# POWER.net
KiCad netlist of a schematic drawn in Altium Designer
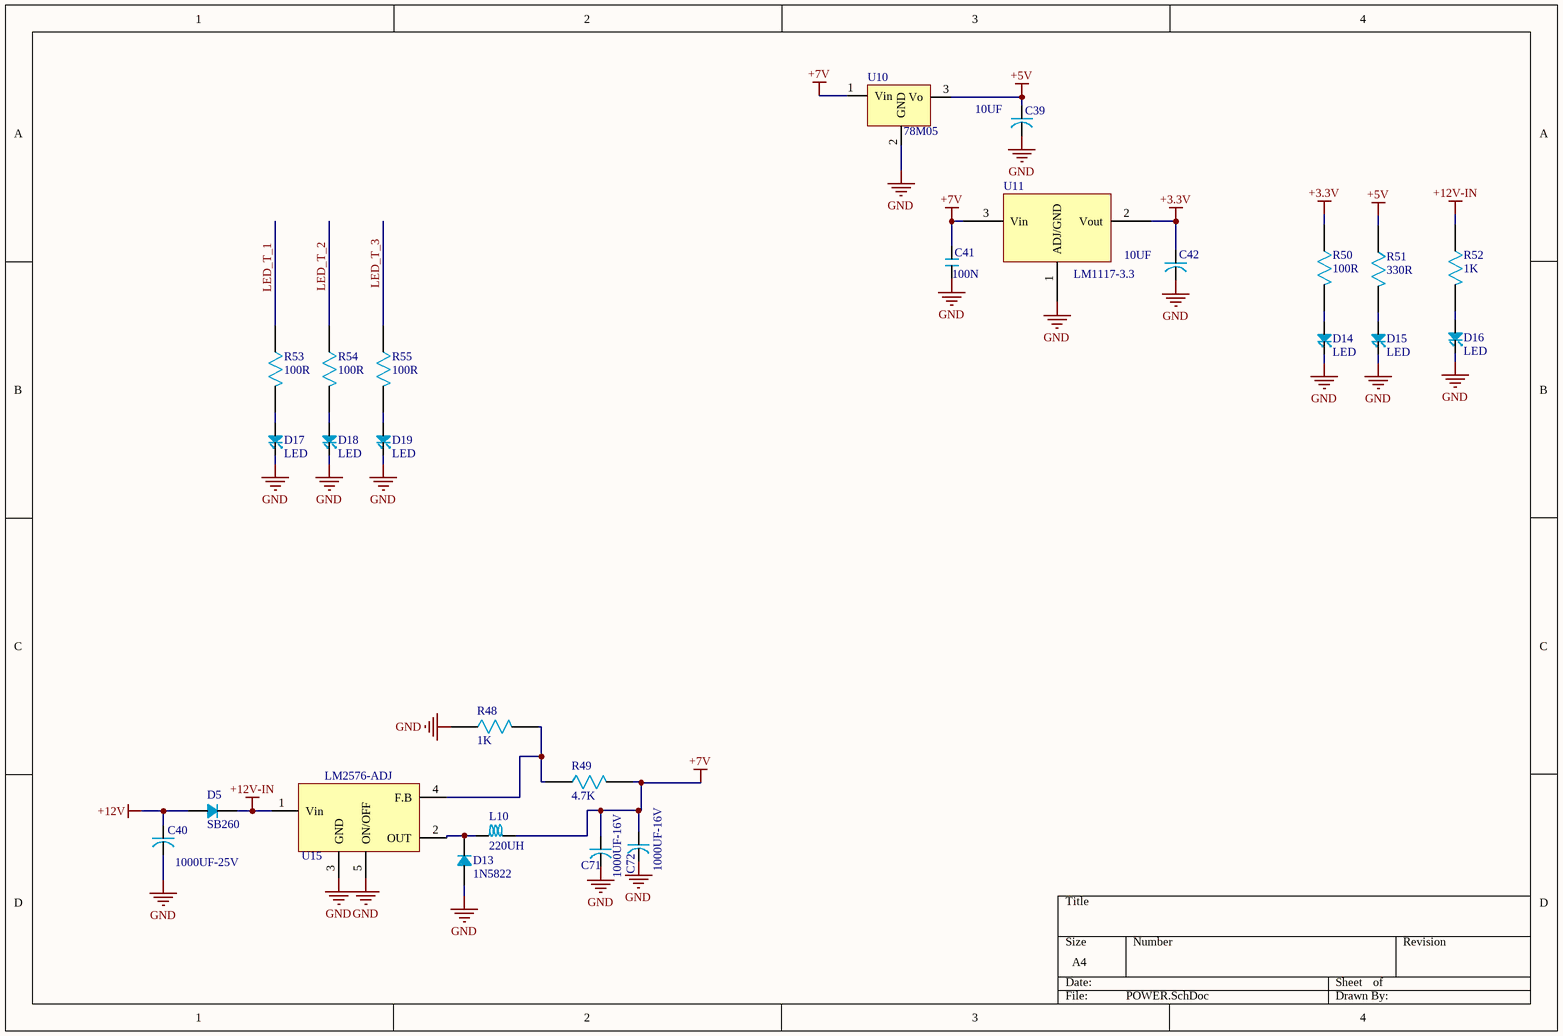
[diagram p0: POWER.SchDoc]

(export (version "E")
  (design (tool "Eeschema 10.0.6"))
  (components
    (comp (ref "C39") (value "10UF") (footprint "1206") (libsource (lib "") (part "CAP_POL_1")))
    (comp (ref "C40") (value "1000UF-25V") (footprint "RB.2/.4") (libsource (lib "") (part "CAP_POL_2")))
    (comp (ref "C41") (value "100N") (footprint "1206") (libsource (lib "R_L_C_V") (part "CAP")))
    (comp (ref "C42") (value "10UF") (footprint "1206") (libsource (lib "") (part "CAP_POL_1")))
    (comp (ref "C71") (value "1000UF-16V") (footprint "RB.2/.4") (libsource (lib "My_lib") (part "CAP_POL")))
    (comp (ref "C72") (value "1000UF-16V") (footprint "RB.2/.4") (libsource (lib "") (part "CAP_POL_1")))
    (comp (ref "D5") (value "SB260") (footprint "DIODE0.1") (libsource (lib "My_lib") (part "DIODE")))
    (comp (ref "D13") (value "1N5822") (footprint "SOD-123-B") (libsource (lib "R_L_C_V") (part "DIODE")))
    (comp (ref "D14") (value "LED") (footprint "0603") (libsource (lib "My_lib") (part "LED")))
    (comp (ref "D15") (value "LED") (footprint "0603") (libsource (lib "My_lib") (part "LED")))
    (comp (ref "D16") (value "LED") (footprint "0603") (libsource (lib "My_lib") (part "LED")))
    (comp (ref "D17") (value "LED") (footprint "0603") (libsource (lib "My_lib") (part "LED")))
    (comp (ref "D18") (value "LED") (footprint "0603") (libsource (lib "My_lib") (part "LED")))
    (comp (ref "D19") (value "LED") (footprint "0603") (libsource (lib "My_lib") (part "LED")))
    (comp (ref "L10") (value "220UH") (footprint "SELF_SMD_CD75") (libsource (lib "R_L_C_V") (part "SELF")))
    (comp (ref "R48") (value "1K") (footprint "1206") (libsource (lib "My_lib") (part "RES")))
    (comp (ref "R49") (value "4.7K") (footprint "1206") (libsource (lib "My_lib") (part "RES")))
    (comp (ref "R50") (value "100R") (footprint "0603") (libsource (lib "My_lib") (part "RES")))
    (comp (ref "R51") (value "330R") (footprint "0603") (libsource (lib "My_lib") (part "RES")))
    (comp (ref "R52") (value "1K") (footprint "0603") (libsource (lib "My_lib") (part "RES")))
    (comp (ref "R53") (value "100R") (footprint "0603") (libsource (lib "My_lib") (part "RES")))
    (comp (ref "R54") (value "100R") (footprint "0603") (libsource (lib "My_lib") (part "RES")))
    (comp (ref "R55") (value "100R") (footprint "0603") (libsource (lib "My_lib") (part "RES")))
    (comp (ref "U10") (value "78M05") (footprint "DPAK") (libsource (lib "My_lib") (part "REG")))
    (comp (ref "U11") (value "LM1117-3.3") (footprint "TO-252") (libsource (lib "MY_IC") (part "LM1117")))
    (comp (ref "U15") (value "LM2576-ADJ") (footprint "CASE936A") (libsource (lib "MY_IC") (part "LM2576")))
  )
  (nets
    (net (code "1") (name "+3.3V") (class "Default")
      (node (ref "C42") (pin "1") (pintype "passive"))
      (node (ref "R50") (pin "1") (pintype "passive"))
      (node (ref "U11") (pin "2") (pinfunction "Vout_2") (pintype "passive"))
    )
    (net (code "2") (name "+5V") (class "Default")
      (node (ref "C39") (pin "1") (pintype "passive"))
      (node (ref "R51") (pin "1") (pintype "passive"))
      (node (ref "U10") (pin "3") (pinfunction "Vo_3") (pintype "passive"))
    )
    (net (code "3") (name "+7V") (class "Default")
      (node (ref "C41") (pin "2") (pintype "passive"))
      (node (ref "C71") (pin "1") (pintype "passive"))
      (node (ref "C72") (pin "1") (pintype "passive"))
      (node (ref "L10") (pin "2") (pintype "passive"))
      (node (ref "R49") (pin "2") (pintype "passive"))
      (node (ref "U10") (pin "1") (pinfunction "Vin_1") (pintype "passive"))
      (node (ref "U11") (pin "3") (pinfunction "Vin_3") (pintype "passive"))
    )
    (net (code "4") (name "+12V") (class "Default")
      (node (ref "C40") (pin "1") (pintype "passive"))
      (node (ref "D5") (pin "1") (pintype "passive"))
    )
    (net (code "5") (name "+12V-IN") (class "Default")
      (node (ref "D5") (pin "2") (pintype "passive"))
      (node (ref "R52") (pin "1") (pintype "passive"))
      (node (ref "U15") (pin "1") (pinfunction "Vin_1") (pintype "passive"))
    )
    (net (code "6") (name "/LED_T_1") (class "Default") (node (ref "R53") (pin "1") (pintype "passive")))
    (net (code "7") (name "/LED_T_2") (class "Default") (node (ref "R54") (pin "1") (pintype "passive")))
    (net (code "8") (name "/LED_T_3") (class "Default") (node (ref "R55") (pin "1") (pintype "passive")))
    (net (code "9") (name "GND") (class "Default")
      (node (ref "C39") (pin "2") (pintype "passive"))
      (node (ref "C40") (pin "2") (pintype "passive"))
      (node (ref "C41") (pin "1") (pintype "passive"))
      (node (ref "C42") (pin "2") (pintype "passive"))
      (node (ref "C71") (pin "2") (pintype "passive"))
      (node (ref "C72") (pin "2") (pintype "passive"))
      (node (ref "D13") (pin "1") (pintype "passive"))
      (node (ref "D14") (pin "2") (pintype "passive"))
      (node (ref "D15") (pin "2") (pintype "passive"))
      (node (ref "D16") (pin "2") (pintype "passive"))
      (node (ref "D17") (pin "2") (pintype "passive"))
      (node (ref "D18") (pin "2") (pintype "passive"))
      (node (ref "D19") (pin "2") (pintype "passive"))
      (node (ref "R48") (pin "1") (pintype "passive"))
      (node (ref "U10") (pin "2") (pinfunction "GND_2") (pintype "passive"))
      (node (ref "U11") (pin "1") (pinfunction "ADJ/GND_1") (pintype "passive"))
      (node (ref "U15") (pin "3") (pinfunction "GND_3") (pintype "passive"))
      (node (ref "U15") (pin "5") (pinfunction "ON/OFF_5") (pintype "passive"))
    )
    (net (code "10") (name "Net-(D14-Pad1)") (class "Default")
      (node (ref "D14") (pin "1") (pintype "passive"))
      (node (ref "R50") (pin "2") (pintype "passive"))
    )
    (net (code "11") (name "Net-(D15-Pad1)") (class "Default")
      (node (ref "D15") (pin "1") (pintype "passive"))
      (node (ref "R51") (pin "2") (pintype "passive"))
    )
    (net (code "12") (name "Net-(D16-Pad1)") (class "Default")
      (node (ref "D16") (pin "1") (pintype "passive"))
      (node (ref "R52") (pin "2") (pintype "passive"))
    )
    (net (code "13") (name "Net-(D17-Pad1)") (class "Default")
      (node (ref "D17") (pin "1") (pintype "passive"))
      (node (ref "R53") (pin "2") (pintype "passive"))
    )
    (net (code "14") (name "Net-(D18-Pad1)") (class "Default")
      (node (ref "D18") (pin "1") (pintype "passive"))
      (node (ref "R54") (pin "2") (pintype "passive"))
    )
    (net (code "15") (name "Net-(D19-Pad1)") (class "Default")
      (node (ref "D19") (pin "1") (pintype "passive"))
      (node (ref "R55") (pin "2") (pintype "passive"))
    )
    (net (code "16") (name "Net-(U15-F.B)") (class "Default")
      (node (ref "R48") (pin "2") (pintype "passive"))
      (node (ref "R49") (pin "1") (pintype "passive"))
      (node (ref "U15") (pin "4") (pinfunction "F.B_4") (pintype "passive"))
    )
    (net (code "17") (name "Net-(U15-OUT)") (class "Default")
      (node (ref "D13") (pin "2") (pintype "passive"))
      (node (ref "L10") (pin "1") (pintype "passive"))
      (node (ref "U15") (pin "2") (pinfunction "OUT_2") (pintype "passive"))
    )
  )
)
